# FSR.net
KiCad netlist of a schematic drawn in Altium Designer
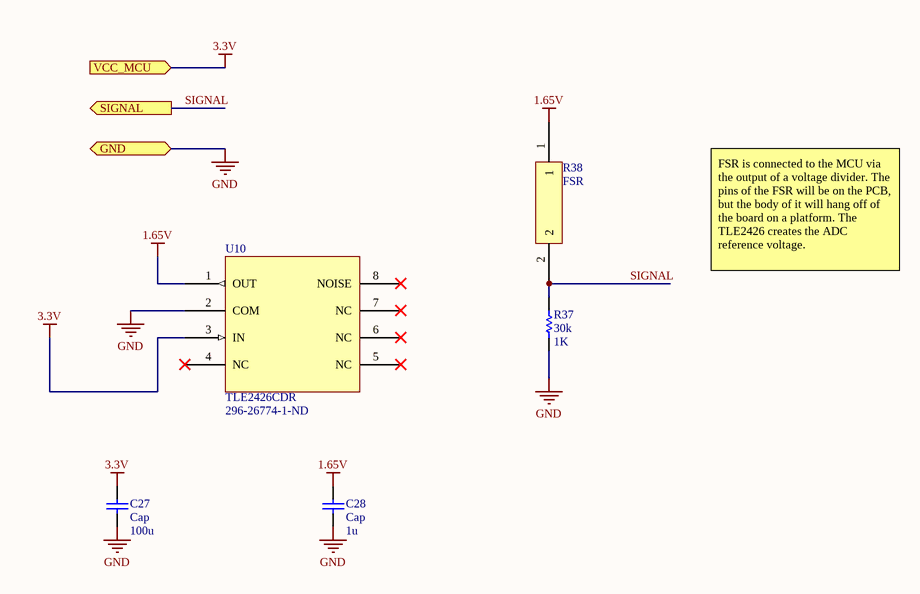
[diagram p0: FSR.SchDoc]

(export (version "E")
  (design (tool "Eeschema 10.0.6"))
  (components
    (comp (ref "C27")
      (value "Cap")
      (footprint "C0805")
      (description "Capacitor")
      (fields (field (name "ALTIUM_VALUE") "100u") (field (name "PUBLISHER") "Altium Limited"))
      (libsource (lib "Miscellaneous Devices") (part "Cap"))
    )
    (comp (ref "C28")
      (value "Cap")
      (footprint "C0805")
      (description "Capacitor")
      (fields (field (name "ALTIUM_VALUE") "1u") (field (name "PUBLISHER") "Altium Limited"))
      (libsource (lib "Miscellaneous Devices") (part "Cap"))
    )
    (comp (ref "R37")
      (value "30k")
      (footprint "6-0805_L")
      (description "Resistor")
      (fields (field (name "ALTIUM_VALUE") "1K") (field (name "PUBLISHER") "Altium Limited"))
      (libsource (lib "Miscellaneous Devices") (part "Res1"))
    )
    (comp (ref "R38")
      (value "FSR")
      (footprint "HDR1X2H")
      (description "Force Sensing Resistor")
      (libsource (lib "Iot_Medicine") (part "FSR-1075-406"))
    )
    (comp (ref "U10")
      (value "TLE2426CDR")
      (footprint "TLE2426CDR")
      (description "Rail Splitter IC")
      (fields
        (field (name "MANUFACTURER") "Texas Instruments")
        (field (name "TOLERANCE") "1%")
        (field (name "SUPPLIER PART NUMBER 1") "296-26774-1-ND")
      )
      (libsource (lib "VoltageManagementComponents") (part "TLE2426"))
    )
  )
  (nets
    (net (code "1") (name "/SIGNAL") (class "Default")
      (node (ref "R37") (pin "1") (pinfunction "1_1") (pintype "passive"))
      (node (ref "R38") (pin "2") (pinfunction "2_2") (pintype "passive"))
    )
    (net (code "2") (name "1.65V") (class "Default")
      (node (ref "C28") (pin "2") (pinfunction "2_2") (pintype "passive"))
      (node (ref "R38") (pin "1") (pinfunction "1_1") (pintype "passive"))
      (node (ref "U10") (pin "1") (pinfunction "OUT_1") (pintype "output"))
    )
    (net (code "3") (name "3.3V") (class "Default")
      (node (ref "C27") (pin "2") (pinfunction "2_2") (pintype "passive"))
      (node (ref "U10") (pin "3") (pinfunction "IN_3") (pintype "input"))
    )
    (net (code "4") (name "GND") (class "Default")
      (node (ref "C27") (pin "1") (pinfunction "1_1") (pintype "passive"))
      (node (ref "C28") (pin "1") (pinfunction "1_1") (pintype "passive"))
      (node (ref "R37") (pin "2") (pinfunction "2_2") (pintype "passive"))
      (node (ref "U10") (pin "2") (pinfunction "COM_2") (pintype "power_in"))
    )
    (net (code "5") (name "unconnected-(U10-NC-Pad4)") (class "Default")
      (node (ref "U10") (pin "4") (pinfunction "NC_4") (pintype "passive+no_connect"))
    )
    (net (code "6") (name "unconnected-(U10-NC-Pad5)") (class "Default")
      (node (ref "U10") (pin "5") (pinfunction "NC_5") (pintype "passive+no_connect"))
    )
    (net (code "7") (name "unconnected-(U10-NC-Pad6)") (class "Default")
      (node (ref "U10") (pin "6") (pinfunction "NC_6") (pintype "passive+no_connect"))
    )
    (net (code "8") (name "unconnected-(U10-NC-Pad7)") (class "Default")
      (node (ref "U10") (pin "7") (pinfunction "NC_7") (pintype "passive+no_connect"))
    )
    (net (code "9") (name "unconnected-(U10-NOISE-Pad8)") (class "Default")
      (node (ref "U10") (pin "8") (pinfunction "NOISE_8") (pintype "passive+no_connect"))
    )
  )
)
